# SH10_-_BMS.net
KiCad netlist of a schematic drawn in Altium Designer
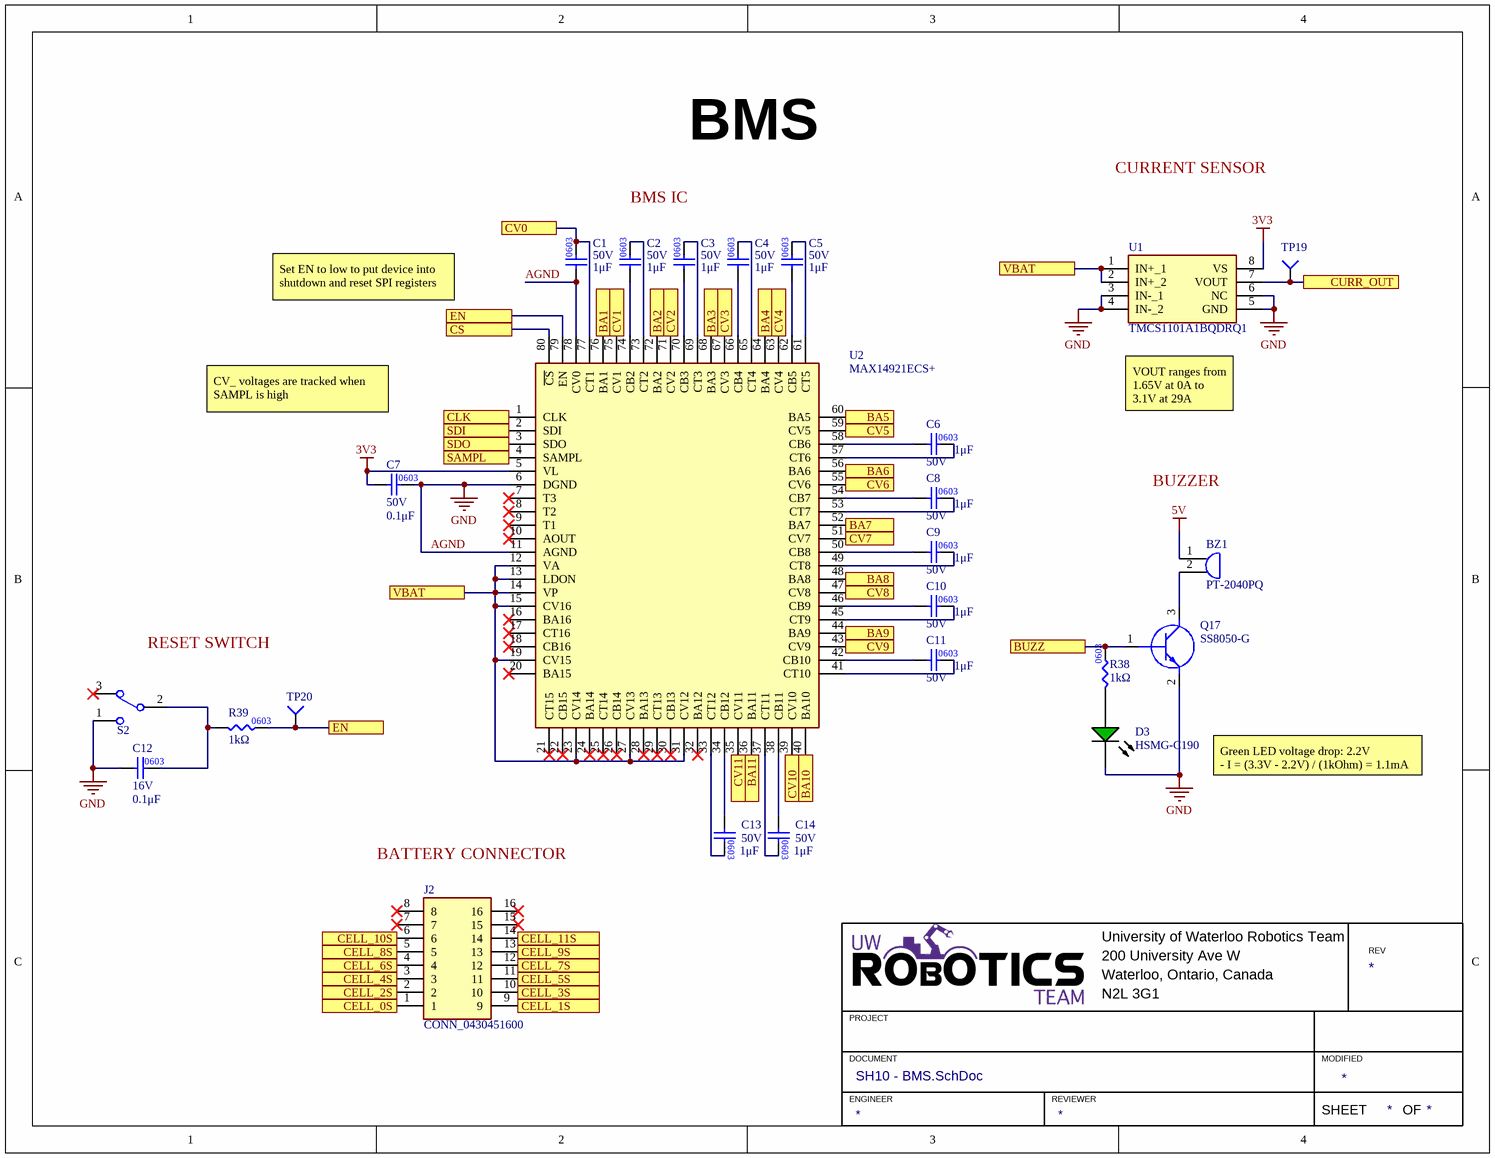
[diagram p0: SH10 - BMS.SchDoc]

(export (version "E")
  (design (tool "Eeschema 10.0.6"))
  (components
    (comp (ref "BZ1")
      (value "PT-2040PQ")
      (footprint "PT2040PQ")
      (description "Loudspeaker or Buzzer")
      (fields (field (name "MOUSER PART NUMBER") "539-PT2040PQ"))
      (libsource (lib "UWRT_Schematic_Library_2020") (part "PT-2040PQ"))
    )
    (comp (ref "C1")
      (value "1μF")
      (footprint "CAP0603")
      (description "CAP CER 1UF 50V X6S 0603")
      (fields (field (name "VOLTAGE RATING") "50V") (field (name "Comment") "CAP_1uF_50V_0603"))
      (libsource (lib "UWRT_Schematic_Library_2020") (part "CAP_1uF_50V_0603"))
    )
    (comp (ref "C2")
      (value "1μF")
      (footprint "CAP0603")
      (description "CAP CER 1UF 50V X6S 0603")
      (fields (field (name "VOLTAGE RATING") "50V") (field (name "Comment") "CAP_1uF_50V_0603"))
      (libsource (lib "UWRT_Schematic_Library_2020") (part "CAP_1uF_50V_0603"))
    )
    (comp (ref "C3")
      (value "1μF")
      (footprint "CAP0603")
      (description "CAP CER 1UF 50V X6S 0603")
      (fields (field (name "VOLTAGE RATING") "50V") (field (name "Comment") "CAP_1uF_50V_0603"))
      (libsource (lib "UWRT_Schematic_Library_2020") (part "CAP_1uF_50V_0603"))
    )
    (comp (ref "C4")
      (value "1μF")
      (footprint "CAP0603")
      (description "CAP CER 1UF 50V X6S 0603")
      (fields (field (name "VOLTAGE RATING") "50V") (field (name "Comment") "CAP_1uF_50V_0603"))
      (libsource (lib "UWRT_Schematic_Library_2020") (part "CAP_1uF_50V_0603"))
    )
    (comp (ref "C5")
      (value "1μF")
      (footprint "CAP0603")
      (description "CAP CER 1UF 50V X6S 0603")
      (fields (field (name "VOLTAGE RATING") "50V") (field (name "Comment") "CAP_1uF_50V_0603"))
      (libsource (lib "UWRT_Schematic_Library_2020") (part "CAP_1uF_50V_0603"))
    )
    (comp (ref "C6")
      (value "1μF")
      (footprint "CAP0603")
      (description "CAP CER 1UF 50V X6S 0603")
      (fields (field (name "VOLTAGE RATING") "50V") (field (name "Comment") "CAP_1uF_50V_0603"))
      (libsource (lib "UWRT_Schematic_Library_2020") (part "CAP_1uF_50V_0603"))
    )
    (comp (ref "C7")
      (value "0.1μF")
      (footprint "CAP0603")
      (description "CAP CER 0.1UF 50V X7R 0603")
      (fields (field (name "VOLTAGE RATING") "50V") (field (name "Comment") "CAP_0.1uF_50V_0603"))
      (libsource (lib "UWRT_Schematic_Library_2020") (part "CAP_0.1uF_50V_0603"))
    )
    (comp (ref "C8")
      (value "1μF")
      (footprint "CAP0603")
      (description "CAP CER 1UF 50V X6S 0603")
      (fields (field (name "VOLTAGE RATING") "50V") (field (name "Comment") "CAP_1uF_50V_0603"))
      (libsource (lib "UWRT_Schematic_Library_2020") (part "CAP_1uF_50V_0603"))
    )
    (comp (ref "C9")
      (value "1μF")
      (footprint "CAP0603")
      (description "CAP CER 1UF 50V X6S 0603")
      (fields (field (name "VOLTAGE RATING") "50V") (field (name "Comment") "CAP_1uF_50V_0603"))
      (libsource (lib "UWRT_Schematic_Library_2020") (part "CAP_1uF_50V_0603"))
    )
    (comp (ref "C10")
      (value "1μF")
      (footprint "CAP0603")
      (description "CAP CER 1UF 50V X6S 0603")
      (fields (field (name "VOLTAGE RATING") "50V") (field (name "Comment") "CAP_1uF_50V_0603"))
      (libsource (lib "UWRT_Schematic_Library_2020") (part "CAP_1uF_50V_0603"))
    )
    (comp (ref "C11")
      (value "1μF")
      (footprint "CAP0603")
      (description "CAP CER 1UF 50V X6S 0603")
      (fields (field (name "VOLTAGE RATING") "50V") (field (name "Comment") "CAP_1uF_50V_0603"))
      (libsource (lib "UWRT_Schematic_Library_2020") (part "CAP_1uF_50V_0603"))
    )
    (comp (ref "C12")
      (value "0.1μF")
      (footprint "CAP0603")
      (description "CAP CER 0.1UF 16V X7R 0603")
      (fields (field (name "VOLTAGE RATING") "16V") (field (name "Comment") "CAP_0.1uF_16V_0603"))
      (libsource (lib "UWRT_Schematic_Library_2020") (part "CAP_0.1uF_16V_0603"))
    )
    (comp (ref "C13")
      (value "1μF")
      (footprint "CAP0603")
      (description "CAP CER 1UF 50V X6S 0603")
      (fields (field (name "VOLTAGE RATING") "50V") (field (name "Comment") "CAP_1uF_50V_0603"))
      (libsource (lib "UWRT_Schematic_Library_2020") (part "CAP_1uF_50V_0603"))
    )
    (comp (ref "C14")
      (value "1μF")
      (footprint "CAP0603")
      (description "CAP CER 1UF 50V X6S 0603")
      (fields (field (name "VOLTAGE RATING") "50V") (field (name "Comment") "CAP_1uF_50V_0603"))
      (libsource (lib "UWRT_Schematic_Library_2020") (part "CAP_1uF_50V_0603"))
    )
    (comp (ref "D3")
      (value "HSMG-C190")
      (footprint "AVAG-HSMX-C190_V")
      (description "Chip LED, Green, 2.2 V, -40 to 85 degC, 2-Pin SMD, RoHS, Tape and Reel")
      (libsource (lib "Altium Content Vault") (part "LED-GREEN-AK-2"))
    )
    (comp (ref "J2")
      (value "CONN_0430451600")
      (footprint "0430451600")
      (description "Connector 16 Pin AJX")
      (fields (field (name "MANUFACTURER_PART_NUMBER") "0430451600"))
      (libsource (lib "UWRT_Schematic_Library_2020") (part "CONN_0430451600"))
    )
    (comp (ref "Q17")
      (value "NPN_40V_1.5A")
      (footprint "SOT23-3")
      (description "TRANS NPN 40V 1.5A SOT23")
      (fields
        (field (name "MOUSER PART NUMBER") "750-SS8050-G")
        (field (name "ARROW PART NUMBER") "SS8050-G")
        (field (name "MANUFACTURER_PART_NUMBER") "SS8050-G")
      )
      (libsource (lib "UWRT_Schematic_Library_2020") (part "NPN_40V_1.5A"))
    )
    (comp (ref "R38")
      (value "1kΩ")
      (footprint "RES0603")
      (description "RES 1K OHM 5% 1/10W 0603")
      (fields (field (name "Comment") "RES_1kΩ_0603_5%"))
      (libsource (lib "UWRT_Schematic_Library_2020") (part "RES_1kΩ_0603_5%"))
    )
    (comp (ref "R39")
      (value "1kΩ")
      (footprint "RES0603")
      (description "RES 1K OHM 5% 1/10W 0603")
      (fields (field (name "Comment") "RES_1kΩ_0603_5%"))
      (libsource (lib "UWRT_Schematic_Library_2020") (part "RES_1kΩ_0603_5%"))
    )
    (comp (ref "S2")
      (value "SW_TOGGLE_SPDT")
      (footprint "100SP1T1B4M2QE")
      (description "SWITCH TOGGLE SPDT 5A 120V")
      (libsource (lib "UWRT_Schematic_Library_2020") (part "SW_TOGGLE_SPDT"))
    )
    (comp (ref "TP19")
      (value "TESTPOINT_1MM_SQUARE")
      (footprint "TESTPOINT_SQUARE_1MM")
      (description "CURR_OUT")
      (libsource (lib "UWRT_Schematic_Library_2020") (part "TESTPOINT_1MM_SQUARE"))
    )
    (comp (ref "TP20")
      (value "TESTPOINT_1MM_SQUARE")
      (footprint "TESTPOINT_SQUARE_1MM")
      (description "TESTPOINT 1MM SQUARE")
      (libsource (lib "UWRT_Schematic_Library_2020") (part "TESTPOINT_1MM_SQUARE"))
    )
    (comp (ref "U1")
      (value "TMCS1101A1BQDRQ1")
      (footprint "SOIC127P600X175-8N")
      (description "Hall-Effect Current Sensor")
      (fields
        (field (name "MOUSER PART NUMBER") "595-TMCS1101A3BQDRQ1")
        (field (name "ARROW PART NUMBER") "TMCS1101A3BQDRQ1")
      )
      (libsource (lib "UWRT_Schematic_Library_2020") (part "TMCS1101A1BQDRQ1"))
    )
    (comp (ref "U2")
      (value "MAX14921ECS+")
      (footprint "QFP50P1400X1400X120-80N")
      (description "IC 16s BMS")
      (fields (field (name "MOUSER PART NUMBER") "700-MAX14921ECS+"))
      (libsource (lib "UWRT_Schematic_Library_2020") (part "MAX14921ECS+"))
    )
  )
  (nets
    (net (code "1") (name "/BA1") (class "Default")
      (node (ref "U2") (pin "76") (pinfunction "BA1_76") (pintype "passive"))
    )
    (net (code "2") (name "/BA2") (class "Default")
      (node (ref "U2") (pin "72") (pinfunction "BA2_72") (pintype "passive"))
    )
    (net (code "3") (name "/BA3") (class "Default")
      (node (ref "U2") (pin "68") (pinfunction "BA3_68") (pintype "passive"))
    )
    (net (code "4") (name "/BA4") (class "Default")
      (node (ref "U2") (pin "64") (pinfunction "BA4_64") (pintype "passive"))
    )
    (net (code "5") (name "/BA5") (class "Default")
      (node (ref "U2") (pin "60") (pinfunction "BA5_60") (pintype "passive"))
    )
    (net (code "6") (name "/BA6") (class "Default")
      (node (ref "U2") (pin "56") (pinfunction "BA6_56") (pintype "passive"))
    )
    (net (code "7") (name "/BA7") (class "Default")
      (node (ref "U2") (pin "52") (pinfunction "BA7_52") (pintype "passive"))
    )
    (net (code "8") (name "/BA8") (class "Default")
      (node (ref "U2") (pin "48") (pinfunction "BA8_48") (pintype "passive"))
    )
    (net (code "9") (name "/BA9") (class "Default")
      (node (ref "U2") (pin "44") (pinfunction "BA9_44") (pintype "passive"))
    )
    (net (code "10") (name "/BA10") (class "Default")
      (node (ref "U2") (pin "40") (pinfunction "BA10_40") (pintype "passive"))
    )
    (net (code "11") (name "/BA11") (class "Default")
      (node (ref "U2") (pin "36") (pinfunction "BA11_36") (pintype "passive"))
    )
    (net (code "12") (name "/BUZZ") (class "Default")
      (node (ref "Q17") (pin "1") (pinfunction "B_1") (pintype "passive"))
      (node (ref "R38") (pin "2") (pinfunction "2_2") (pintype "passive"))
    )
    (net (code "13") (name "/CELL_0S") (class "Default")
      (node (ref "J2") (pin "1") (pinfunction "1_1") (pintype "passive"))
    )
    (net (code "14") (name "/CELL_1S") (class "Default")
      (node (ref "J2") (pin "9") (pinfunction "9_9") (pintype "passive"))
    )
    (net (code "15") (name "/CELL_2S") (class "Default")
      (node (ref "J2") (pin "2") (pinfunction "2_2") (pintype "passive"))
    )
    (net (code "16") (name "/CELL_3S") (class "Default")
      (node (ref "J2") (pin "10") (pinfunction "10_10") (pintype "passive"))
    )
    (net (code "17") (name "/CELL_4S") (class "Default")
      (node (ref "J2") (pin "3") (pinfunction "3_3") (pintype "passive"))
    )
    (net (code "18") (name "/CELL_5S") (class "Default")
      (node (ref "J2") (pin "11") (pinfunction "11_11") (pintype "passive"))
    )
    (net (code "19") (name "/CELL_6S") (class "Default")
      (node (ref "J2") (pin "4") (pinfunction "4_4") (pintype "passive"))
    )
    (net (code "20") (name "/CELL_7S") (class "Default")
      (node (ref "J2") (pin "12") (pinfunction "12_12") (pintype "passive"))
    )
    (net (code "21") (name "/CELL_8S") (class "Default")
      (node (ref "J2") (pin "5") (pinfunction "5_5") (pintype "passive"))
    )
    (net (code "22") (name "/CELL_9S") (class "Default")
      (node (ref "J2") (pin "13") (pinfunction "13_13") (pintype "passive"))
    )
    (net (code "23") (name "/CELL_10S") (class "Default")
      (node (ref "J2") (pin "6") (pinfunction "6_6") (pintype "passive"))
    )
    (net (code "24") (name "/CELL_11S") (class "Default")
      (node (ref "J2") (pin "14") (pinfunction "14_14") (pintype "passive"))
    )
    (net (code "25") (name "/CLK") (class "Default")
      (node (ref "U2") (pin "1") (pinfunction "CLK_1") (pintype "passive"))
    )
    (net (code "26") (name "/CS") (class "Default")
      (node (ref "U2") (pin "80") (pinfunction "~{CS}_80") (pintype "passive"))
    )
    (net (code "27") (name "/CURR_OUT") (class "Default")
      (node (ref "TP19") (pin "1") (pinfunction "=value_1") (pintype "passive"))
      (node (ref "U1") (pin "7") (pinfunction "VOUT_7") (pintype "passive"))
    )
    (net (code "28") (name "/CV0") (class "Default")
      (node (ref "C1") (pin "2") (pinfunction "2_2") (pintype "passive"))
      (node (ref "U2") (pin "77") (pinfunction "CT1_77") (pintype "passive"))
    )
    (net (code "29") (name "/CV1") (class "Default")
      (node (ref "U2") (pin "75") (pinfunction "CV1_75") (pintype "passive"))
    )
    (net (code "30") (name "/CV2") (class "Default")
      (node (ref "U2") (pin "71") (pinfunction "CV2_71") (pintype "passive"))
    )
    (net (code "31") (name "/CV3") (class "Default")
      (node (ref "U2") (pin "67") (pinfunction "CV3_67") (pintype "passive"))
    )
    (net (code "32") (name "/CV4") (class "Default")
      (node (ref "U2") (pin "63") (pinfunction "CV4_63") (pintype "passive"))
    )
    (net (code "33") (name "/CV5") (class "Default")
      (node (ref "U2") (pin "59") (pinfunction "CV5_59") (pintype "passive"))
    )
    (net (code "34") (name "/CV6") (class "Default")
      (node (ref "U2") (pin "55") (pinfunction "CV6_55") (pintype "passive"))
    )
    (net (code "35") (name "/CV7") (class "Default")
      (node (ref "U2") (pin "51") (pinfunction "CV7_51") (pintype "passive"))
    )
    (net (code "36") (name "/CV8") (class "Default")
      (node (ref "U2") (pin "47") (pinfunction "CV8_47") (pintype "passive"))
    )
    (net (code "37") (name "/CV9") (class "Default")
      (node (ref "U2") (pin "43") (pinfunction "CV9_43") (pintype "passive"))
    )
    (net (code "38") (name "/CV10") (class "Default")
      (node (ref "U2") (pin "39") (pinfunction "CV10_39") (pintype "passive"))
    )
    (net (code "39") (name "/CV11") (class "Default")
      (node (ref "U2") (pin "35") (pinfunction "CV11_35") (pintype "passive"))
    )
    (net (code "40") (name "/EN") (class "Default")
      (node (ref "R39") (pin "2") (pinfunction "2_2") (pintype "passive"))
      (node (ref "TP20") (pin "1") (pinfunction "=value_1") (pintype "passive"))
      (node (ref "U2") (pin "79") (pinfunction "EN_79") (pintype "passive"))
    )
    (net (code "41") (name "/SAMPL") (class "Default")
      (node (ref "U2") (pin "4") (pinfunction "SAMPL_4") (pintype "passive"))
    )
    (net (code "42") (name "/SDI") (class "Default")
      (node (ref "U2") (pin "2") (pinfunction "SDI_2") (pintype "passive"))
    )
    (net (code "43") (name "/SDO") (class "Default")
      (node (ref "U2") (pin "3") (pinfunction "SDO_3") (pintype "passive"))
    )
    (net (code "44") (name "/VBAT") (class "Default")
      (node (ref "U1") (pin "1") (pinfunction "IN+_1_1") (pintype "passive"))
      (node (ref "U1") (pin "2") (pinfunction "IN+_2_2") (pintype "passive"))
      (node (ref "U2") (pin "12") (pinfunction "VA_12") (pintype "passive"))
      (node (ref "U2") (pin "13") (pinfunction "LDON_13") (pintype "passive"))
      (node (ref "U2") (pin "14") (pinfunction "VP_14") (pintype "passive"))
      (node (ref "U2") (pin "15") (pinfunction "CV16_15") (pintype "passive"))
      (node (ref "U2") (pin "19") (pinfunction "CV15_19") (pintype "passive"))
      (node (ref "U2") (pin "23") (pinfunction "CV14_23") (pintype "passive"))
      (node (ref "U2") (pin "27") (pinfunction "CV13_27") (pintype "passive"))
      (node (ref "U2") (pin "31") (pinfunction "CV12_31") (pintype "passive"))
    )
    (net (code "45") (name "3V3") (class "Default")
      (node (ref "C7") (pin "1") (pinfunction "1_1") (pintype "passive"))
      (node (ref "U1") (pin "8") (pinfunction "VS_8") (pintype "passive"))
      (node (ref "U2") (pin "5") (pinfunction "VL_5") (pintype "passive"))
    )
    (net (code "46") (name "5V") (class "Default")
      (node (ref "BZ1") (pin "1") (pinfunction "1_1") (pintype "passive"))
    )
    (net (code "47") (name "GND") (class "Default")
      (node (ref "C1") (pin "1") (pinfunction "1_1") (pintype "passive"))
      (node (ref "C12") (pin "1") (pinfunction "1_1") (pintype "passive"))
      (node (ref "C7") (pin "2") (pinfunction "2_2") (pintype "passive"))
      (node (ref "D3") (pin "2") (pinfunction "K_2") (pintype "passive"))
      (node (ref "Q17") (pin "2") (pinfunction "E_2") (pintype "passive"))
      (node (ref "S2") (pin "1") (pinfunction "1_1") (pintype "passive"))
      (node (ref "U1") (pin "3") (pinfunction "IN-_1_3") (pintype "passive"))
      (node (ref "U1") (pin "4") (pinfunction "IN-_2_4") (pintype "passive"))
      (node (ref "U1") (pin "5") (pinfunction "GND_5") (pintype "passive"))
      (node (ref "U1") (pin "6") (pinfunction "NC_6") (pintype "passive"))
      (node (ref "U2") (pin "11") (pinfunction "AGND_11") (pintype "passive"))
      (node (ref "U2") (pin "6") (pinfunction "DGND_6") (pintype "passive"))
      (node (ref "U2") (pin "78") (pinfunction "CV0_78") (pintype "passive"))
    )
    (net (code "48") (name "Net-(C12-Pad2)") (class "Default")
      (node (ref "C12") (pin "2") (pinfunction "2_2") (pintype "passive"))
      (node (ref "R39") (pin "1") (pinfunction "1_1") (pintype "passive"))
      (node (ref "S2") (pin "2") (pinfunction "2_2") (pintype "passive"))
    )
    (net (code "49") (name "Net-(D3-A)") (class "Default")
      (node (ref "D3") (pin "1") (pinfunction "A_1") (pintype "passive"))
      (node (ref "R38") (pin "1") (pinfunction "1_1") (pintype "passive"))
    )
    (net (code "50") (name "Net-(Q17-C)") (class "Default")
      (node (ref "BZ1") (pin "2") (pinfunction "2_2") (pintype "passive"))
      (node (ref "Q17") (pin "3") (pinfunction "C_3") (pintype "passive"))
    )
    (net (code "51") (name "Net-(U2-CB2)") (class "Default")
      (node (ref "C2") (pin "1") (pinfunction "1_1") (pintype "passive"))
      (node (ref "U2") (pin "74") (pinfunction "CB2_74") (pintype "passive"))
    )
    (net (code "52") (name "Net-(U2-CB3)") (class "Default")
      (node (ref "C3") (pin "1") (pinfunction "1_1") (pintype "passive"))
      (node (ref "U2") (pin "70") (pinfunction "CB3_70") (pintype "passive"))
    )
    (net (code "53") (name "Net-(U2-CB4)") (class "Default")
      (node (ref "C4") (pin "1") (pinfunction "1_1") (pintype "passive"))
      (node (ref "U2") (pin "66") (pinfunction "CB4_66") (pintype "passive"))
    )
    (net (code "54") (name "Net-(U2-CB5)") (class "Default")
      (node (ref "C5") (pin "1") (pinfunction "1_1") (pintype "passive"))
      (node (ref "U2") (pin "62") (pinfunction "CB5_62") (pintype "passive"))
    )
    (net (code "55") (name "Net-(U2-CB6)") (class "Default")
      (node (ref "C6") (pin "1") (pinfunction "1_1") (pintype "passive"))
      (node (ref "U2") (pin "58") (pinfunction "CB6_58") (pintype "passive"))
    )
    (net (code "56") (name "Net-(U2-CB7)") (class "Default")
      (node (ref "C8") (pin "1") (pinfunction "1_1") (pintype "passive"))
      (node (ref "U2") (pin "54") (pinfunction "CB7_54") (pintype "passive"))
    )
    (net (code "57") (name "Net-(U2-CB8)") (class "Default")
      (node (ref "C9") (pin "1") (pinfunction "1_1") (pintype "passive"))
      (node (ref "U2") (pin "50") (pinfunction "CB8_50") (pintype "passive"))
    )
    (net (code "58") (name "Net-(U2-CB9)") (class "Default")
      (node (ref "C10") (pin "1") (pinfunction "1_1") (pintype "passive"))
      (node (ref "U2") (pin "46") (pinfunction "CB9_46") (pintype "passive"))
    )
    (net (code "59") (name "Net-(U2-CB10)") (class "Default")
      (node (ref "C11") (pin "1") (pinfunction "1_1") (pintype "passive"))
      (node (ref "U2") (pin "42") (pinfunction "CB10_42") (pintype "passive"))
    )
    (net (code "60") (name "Net-(U2-CB11)") (class "Default")
      (node (ref "C14") (pin "1") (pinfunction "1_1") (pintype "passive"))
      (node (ref "U2") (pin "38") (pinfunction "CB11_38") (pintype "passive"))
    )
    (net (code "61") (name "Net-(U2-CB12)") (class "Default")
      (node (ref "C13") (pin "1") (pinfunction "1_1") (pintype "passive"))
      (node (ref "U2") (pin "34") (pinfunction "CB12_34") (pintype "passive"))
    )
    (net (code "62") (name "Net-(U2-CT2)") (class "Default")
      (node (ref "C2") (pin "2") (pinfunction "2_2") (pintype "passive"))
      (node (ref "U2") (pin "73") (pinfunction "CT2_73") (pintype "passive"))
    )
    (net (code "63") (name "Net-(U2-CT3)") (class "Default")
      (node (ref "C3") (pin "2") (pinfunction "2_2") (pintype "passive"))
      (node (ref "U2") (pin "69") (pinfunction "CT3_69") (pintype "passive"))
    )
    (net (code "64") (name "Net-(U2-CT4)") (class "Default")
      (node (ref "C4") (pin "2") (pinfunction "2_2") (pintype "passive"))
      (node (ref "U2") (pin "65") (pinfunction "CT4_65") (pintype "passive"))
    )
    (net (code "65") (name "Net-(U2-CT5)") (class "Default")
      (node (ref "C5") (pin "2") (pinfunction "2_2") (pintype "passive"))
      (node (ref "U2") (pin "61") (pinfunction "CT5_61") (pintype "passive"))
    )
    (net (code "66") (name "Net-(U2-CT6)") (class "Default")
      (node (ref "C6") (pin "2") (pinfunction "2_2") (pintype "passive"))
      (node (ref "U2") (pin "57") (pinfunction "CT6_57") (pintype "passive"))
    )
    (net (code "67") (name "Net-(U2-CT7)") (class "Default")
      (node (ref "C8") (pin "2") (pinfunction "2_2") (pintype "passive"))
      (node (ref "U2") (pin "53") (pinfunction "CT7_53") (pintype "passive"))
    )
    (net (code "68") (name "Net-(U2-CT8)") (class "Default")
      (node (ref "C9") (pin "2") (pinfunction "2_2") (pintype "passive"))
      (node (ref "U2") (pin "49") (pinfunction "CT8_49") (pintype "passive"))
    )
    (net (code "69") (name "Net-(U2-CT9)") (class "Default")
      (node (ref "C10") (pin "2") (pinfunction "2_2") (pintype "passive"))
      (node (ref "U2") (pin "45") (pinfunction "CT9_45") (pintype "passive"))
    )
    (net (code "70") (name "Net-(U2-CT10)") (class "Default")
      (node (ref "C11") (pin "2") (pinfunction "2_2") (pintype "passive"))
      (node (ref "U2") (pin "41") (pinfunction "CT10_41") (pintype "passive"))
    )
    (net (code "71") (name "Net-(U2-CT11)") (class "Default")
      (node (ref "C14") (pin "2") (pinfunction "2_2") (pintype "passive"))
      (node (ref "U2") (pin "37") (pinfunction "CT11_37") (pintype "passive"))
    )
    (net (code "72") (name "Net-(U2-CT12)") (class "Default")
      (node (ref "C13") (pin "2") (pinfunction "2_2") (pintype "passive"))
      (node (ref "U2") (pin "33") (pinfunction "CT12_33") (pintype "passive"))
    )
    (net (code "73") (name "unconnected-(J2-Pad7)") (class "Default")
      (node (ref "J2") (pin "7") (pinfunction "7_7") (pintype "passive+no_connect"))
    )
    (net (code "74") (name "unconnected-(J2-Pad8)") (class "Default")
      (node (ref "J2") (pin "8") (pinfunction "8_8") (pintype "passive+no_connect"))
    )
    (net (code "75") (name "unconnected-(J2-Pad15)") (class "Default")
      (node (ref "J2") (pin "15") (pinfunction "15_15") (pintype "passive+no_connect"))
    )
    (net (code "76") (name "unconnected-(J2-Pad16)") (class "Default")
      (node (ref "J2") (pin "16") (pinfunction "16_16") (pintype "passive+no_connect"))
    )
    (net (code "77") (name "unconnected-(S2-Pad3)") (class "Default")
      (node (ref "S2") (pin "3") (pinfunction "3_3") (pintype "passive+no_connect"))
    )
    (net (code "78") (name "unconnected-(U2-AOUT-Pad10)") (class "Default")
      (node (ref "U2") (pin "10") (pinfunction "AOUT_10") (pintype "passive+no_connect"))
    )
    (net (code "79") (name "unconnected-(U2-BA12-Pad32)") (class "Default")
      (node (ref "U2") (pin "32") (pinfunction "BA12_32") (pintype "passive+no_connect"))
    )
    (net (code "80") (name "unconnected-(U2-BA13-Pad28)") (class "Default")
      (node (ref "U2") (pin "28") (pinfunction "BA13_28") (pintype "passive+no_connect"))
    )
    (net (code "81") (name "unconnected-(U2-BA14-Pad24)") (class "Default")
      (node (ref "U2") (pin "24") (pinfunction "BA14_24") (pintype "passive+no_connect"))
    )
    (net (code "82") (name "unconnected-(U2-BA15-Pad20)") (class "Default")
      (node (ref "U2") (pin "20") (pinfunction "BA15_20") (pintype "passive+no_connect"))
    )
    (net (code "83") (name "unconnected-(U2-BA16-Pad16)") (class "Default")
      (node (ref "U2") (pin "16") (pinfunction "BA16_16") (pintype "passive+no_connect"))
    )
    (net (code "84") (name "unconnected-(U2-CB13-Pad30)") (class "Default")
      (node (ref "U2") (pin "30") (pinfunction "CB13_30") (pintype "passive+no_connect"))
    )
    (net (code "85") (name "unconnected-(U2-CB14-Pad26)") (class "Default")
      (node (ref "U2") (pin "26") (pinfunction "CB14_26") (pintype "passive+no_connect"))
    )
    (net (code "86") (name "unconnected-(U2-CB15-Pad22)") (class "Default")
      (node (ref "U2") (pin "22") (pinfunction "CB15_22") (pintype "passive+no_connect"))
    )
    (net (code "87") (name "unconnected-(U2-CB16-Pad18)") (class "Default")
      (node (ref "U2") (pin "18") (pinfunction "CB16_18") (pintype "passive+no_connect"))
    )
    (net (code "88") (name "unconnected-(U2-CT13-Pad29)") (class "Default")
      (node (ref "U2") (pin "29") (pinfunction "CT13_29") (pintype "passive+no_connect"))
    )
    (net (code "89") (name "unconnected-(U2-CT14-Pad25)") (class "Default")
      (node (ref "U2") (pin "25") (pinfunction "CT14_25") (pintype "passive+no_connect"))
    )
    (net (code "90") (name "unconnected-(U2-CT15-Pad21)") (class "Default")
      (node (ref "U2") (pin "21") (pinfunction "CT15_21") (pintype "passive+no_connect"))
    )
    (net (code "91") (name "unconnected-(U2-CT16-Pad17)") (class "Default")
      (node (ref "U2") (pin "17") (pinfunction "CT16_17") (pintype "passive+no_connect"))
    )
    (net (code "92") (name "unconnected-(U2-T1-Pad9)") (class "Default")
      (node (ref "U2") (pin "9") (pinfunction "T1_9") (pintype "passive+no_connect"))
    )
    (net (code "93") (name "unconnected-(U2-T2-Pad8)") (class "Default")
      (node (ref "U2") (pin "8") (pinfunction "T2_8") (pintype "passive+no_connect"))
    )
    (net (code "94") (name "unconnected-(U2-T3-Pad7)") (class "Default")
      (node (ref "U2") (pin "7") (pinfunction "T3_7") (pintype "passive+no_connect"))
    )
  )
)
